# CP_Sapling.net
KiCad netlist of a schematic drawn in EAGLE
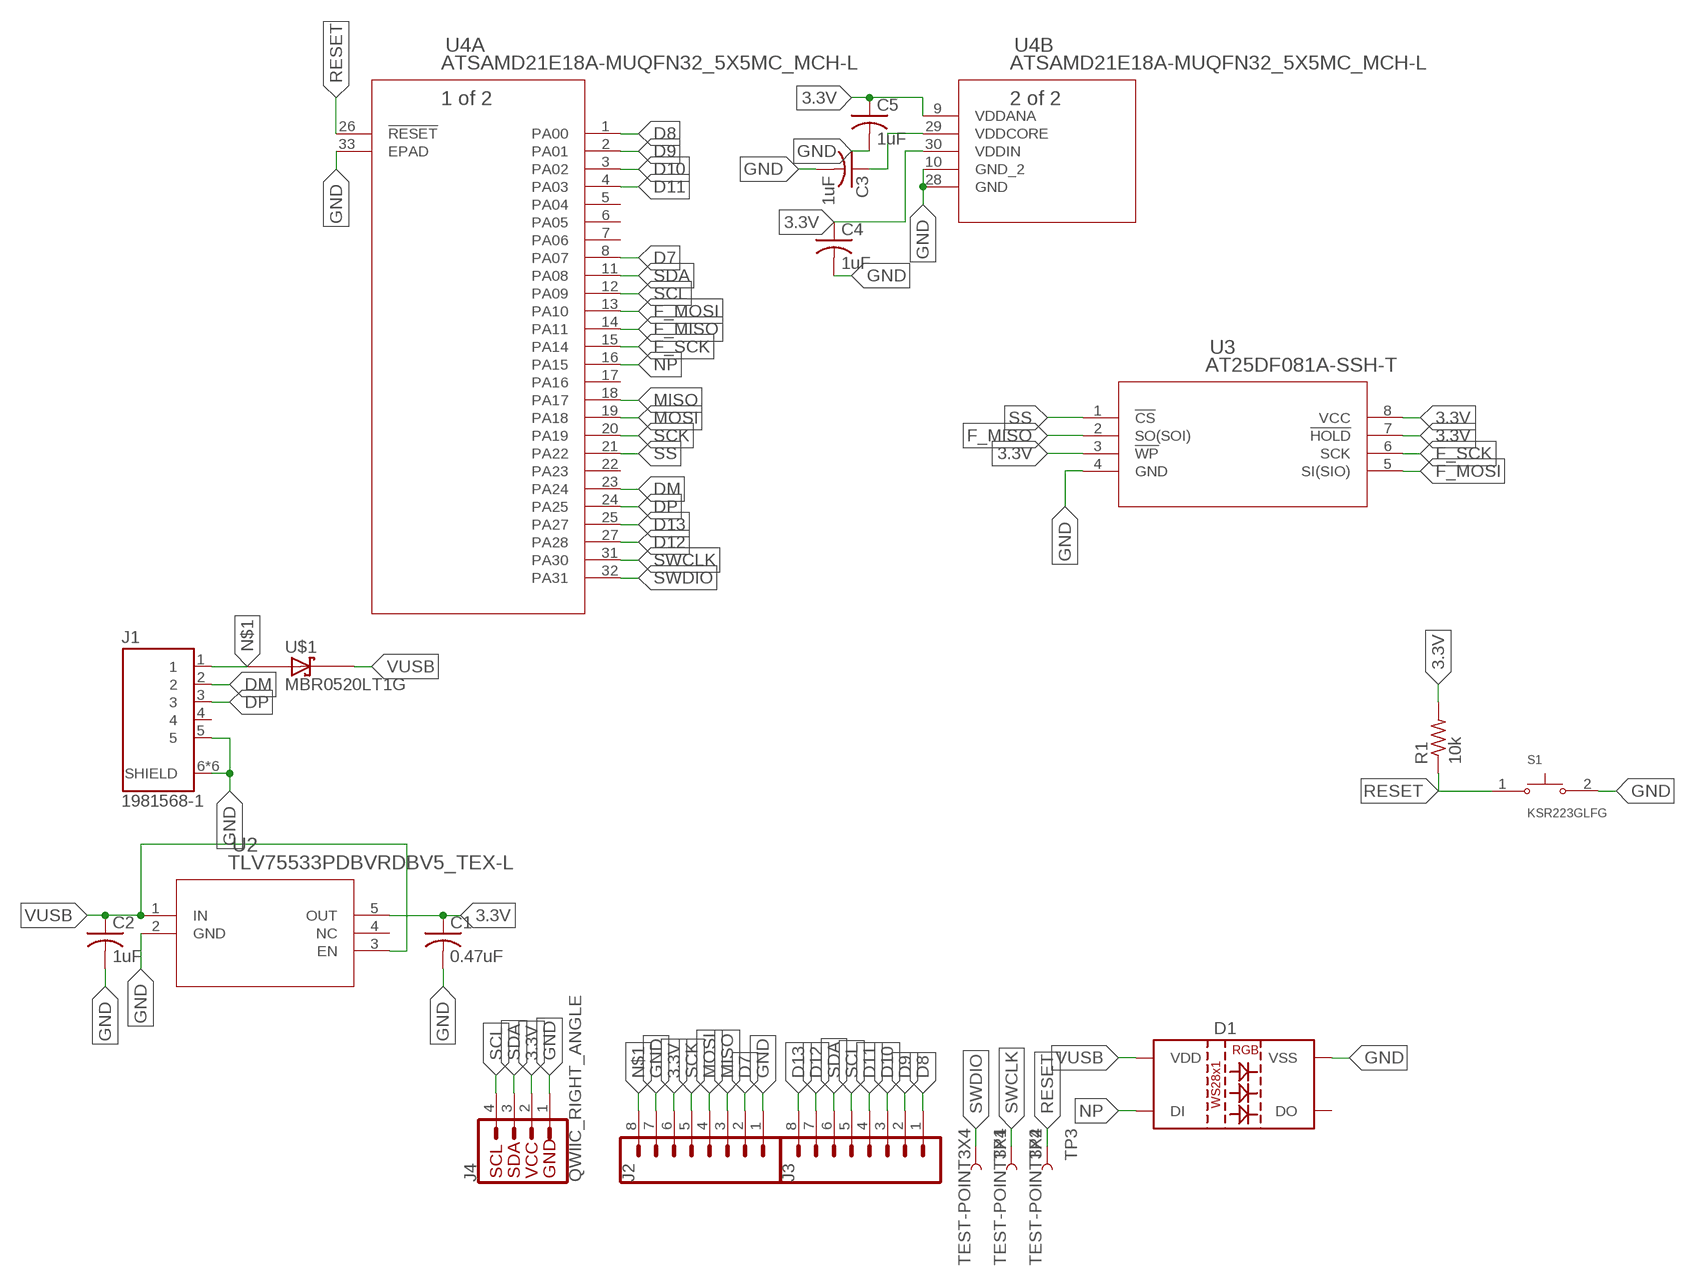
[diagram p0: schematic, sheet 1]

(export (version "E")
  (design (tool "Eeschema 10.0.6"))
  (components
    (comp (ref "C1")
      (value "0.47uF")
      (footprint "eagle-import:C0402")
      (libsource (lib "eagle-import") (part "C-USC0402"))
    )
    (comp (ref "C2")
      (value "1uF")
      (footprint "eagle-import:C0402")
      (libsource (lib "eagle-import") (part "C-USC0402"))
    )
    (comp (ref "C3")
      (value "1uF")
      (footprint "eagle-import:C0402")
      (libsource (lib "eagle-import") (part "C-USC0402"))
    )
    (comp (ref "C4")
      (value "1uF")
      (footprint "eagle-import:C0402")
      (libsource (lib "eagle-import") (part "C-USC0402"))
    )
    (comp (ref "C5")
      (value "1uF")
      (footprint "eagle-import:C0402")
      (libsource (lib "eagle-import") (part "C-USC0402"))
    )
    (comp (ref "D1")
      (value "WS2812B")
      (footprint "eagle-import:WS2812-3535")
      (libsource (lib "eagle-import") (part "WS2812BWS2812B-3535"))
    )
    (comp (ref "J1")
      (value "1981568-1")
      (footprint "eagle-import:TE_1981568-1")
      (fields (field (name "MF") "TE Connectivity") (field (name "MP") "19815681"))
      (libsource (lib "eagle-import") (part "1981568-1"))
    )
    (comp (ref "J2")
      (value "CONN_08NO_SILK_DNP")
      (footprint "eagle-import:1X08_NO_SILK")
      (libsource (lib "eagle-import") (part "CONN_08NO_SILK_DNP"))
    )
    (comp (ref "J3")
      (value "CONN_08NO_SILK_DNP")
      (footprint "eagle-import:1X08_NO_SILK")
      (libsource (lib "eagle-import") (part "CONN_08NO_SILK_DNP"))
    )
    (comp (ref "J4")
      (value "QWIIC_RIGHT_ANGLE")
      (footprint "eagle-import:JST04_1MM_RA")
      (libsource (lib "eagle-import") (part "QWIIC_CONNECTORJS-1MM"))
    )
    (comp (ref "R1")
      (value "10k")
      (footprint "eagle-import:R0402")
      (libsource (lib "eagle-import") (part "R-US_R0402"))
    )
    (comp (ref "S1")
      (value "KSR223GLFG")
      (footprint "eagle-import:SW_KSR223GLFG")
      (fields (field (name "MF") "C&K"))
      (libsource (lib "eagle-import") (part "KSR223GLFG"))
    )
    (comp (ref "TP1")
      (value "TEST-POINT3X4")
      (footprint "eagle-import:PAD.03X.04")
      (libsource (lib "eagle-import") (part "TEST-POINT3X4"))
    )
    (comp (ref "TP2")
      (value "TEST-POINT3X4")
      (footprint "eagle-import:PAD.03X.04")
      (libsource (lib "eagle-import") (part "TEST-POINT3X4"))
    )
    (comp (ref "TP3")
      (value "TEST-POINT3X4")
      (footprint "eagle-import:PAD.03X.04")
      (libsource (lib "eagle-import") (part "TEST-POINT3X4"))
    )
    (comp (ref "U$1")
      (value "MBR0520LT1G")
      (footprint "eagle-import:SOD3716X117(SOD-123)")
      (fields (field (name "MF") "ON Semiconductor"))
      (libsource (lib "eagle-import") (part "MBR0520LT1G"))
    )
    (comp (ref "U2")
      (value "TLV75533PDBVRDBV5_TEX-L")
      (footprint "eagle-import:DBV5_TEX-L")
      (fields
        (field (name "MANUFACTURER_PART_NUMBER") "TLV75533PDBVR")
        (field (name "COPYRIGHT") "Copyright (C) 2018 Accelerated Designs. All rights reserved")
      )
      (libsource (lib "eagle-import") (part "TLV75533PDBVRDBV5_TEX-L"))
    )
    (comp (ref "U3")
      (value "AT25DF081A-SSH-T")
      (footprint "eagle-import:SOIC_AT25DF081_ADO")
      (fields (field (name "COPYRIGHT") "Copyright (C) 2018 Accelerated Designs. All rights reserved"))
      (libsource (lib "eagle-import") (part "AT25DF081A-SSH-T"))
    )
    (comp (ref "U4")
      (value "ATSAMD21E18A-MUQFN32_5X5MC_MCH-L")
      (footprint "eagle-import:QFN32_5X5MC_MCH-L")
      (fields
        (field (name "MANUFACTURER_PART_NUMBER") "ATSAMD21E18A-MU")
        (field (name "COPYRIGHT") "Copyright (C) 2018 Accelerated Designs. All rights reserved")
      )
      (libsource (lib "eagle-import") (part "ATSAMD21E18A-MUQFN32_5X5MC_MCH-L"))
    )
  )
  (nets
    (net (code "1") (name "3.3V") (class "Default")
      (node (ref "C1") (pin "1") (pinfunction "1_1") (pintype "passive"))
      (node (ref "C4") (pin "1") (pinfunction "1_1") (pintype "passive"))
      (node (ref "C5") (pin "1") (pinfunction "1_1") (pintype "passive"))
      (node (ref "J2") (pin "6") (pinfunction "6_6") (pintype "passive"))
      (node (ref "J4") (pin "2") (pinfunction "2_2") (pintype "power_in"))
      (node (ref "R1") (pin "2") (pinfunction "2_2") (pintype "passive"))
      (node (ref "U2") (pin "5") (pinfunction "OUT_5") (pintype "output"))
      (node (ref "U3") (pin "3") (pinfunction "~{WP}_3") (pintype "input"))
      (node (ref "U3") (pin "7") (pinfunction "~{HOLD}_7") (pintype "input"))
      (node (ref "U3") (pin "8") (pinfunction "VCC_8") (pintype "power_in"))
      (node (ref "U4") (pin "30") (pinfunction "VDDIN_30") (pintype "power_in"))
      (node (ref "U4") (pin "9") (pinfunction "VDDANA_9") (pintype "power_in"))
    )
    (net (code "2") (name "D7") (class "Default")
      (node (ref "J2") (pin "2") (pinfunction "2_2") (pintype "passive"))
      (node (ref "U4") (pin "8") (pinfunction "PA07_8") (pintype "bidirectional"))
    )
    (net (code "3") (name "D8") (class "Default")
      (node (ref "J3") (pin "1") (pinfunction "1_1") (pintype "passive"))
      (node (ref "U4") (pin "1") (pinfunction "PA00_1") (pintype "bidirectional"))
    )
    (net (code "4") (name "D9") (class "Default")
      (node (ref "J3") (pin "2") (pinfunction "2_2") (pintype "passive"))
      (node (ref "U4") (pin "2") (pinfunction "PA01_2") (pintype "bidirectional"))
    )
    (net (code "5") (name "D10") (class "Default")
      (node (ref "J3") (pin "3") (pinfunction "3_3") (pintype "passive"))
      (node (ref "U4") (pin "3") (pinfunction "PA02_3") (pintype "bidirectional"))
    )
    (net (code "6") (name "D11") (class "Default")
      (node (ref "J3") (pin "4") (pinfunction "4_4") (pintype "passive"))
      (node (ref "U4") (pin "4") (pinfunction "PA03_4") (pintype "bidirectional"))
    )
    (net (code "7") (name "D12") (class "Default")
      (node (ref "J3") (pin "7") (pinfunction "7_7") (pintype "passive"))
      (node (ref "U4") (pin "27") (pinfunction "PA28_27") (pintype "bidirectional"))
    )
    (net (code "8") (name "D13") (class "Default")
      (node (ref "J3") (pin "8") (pinfunction "8_8") (pintype "passive"))
      (node (ref "U4") (pin "25") (pinfunction "PA27_25") (pintype "bidirectional"))
    )
    (net (code "9") (name "DM") (class "Default")
      (node (ref "J1") (pin "2") (pinfunction "2_2") (pintype "passive"))
      (node (ref "U4") (pin "23") (pinfunction "PA24_23") (pintype "bidirectional"))
    )
    (net (code "10") (name "DP") (class "Default")
      (node (ref "J1") (pin "3") (pinfunction "3_3") (pintype "passive"))
      (node (ref "U4") (pin "24") (pinfunction "PA25_24") (pintype "bidirectional"))
    )
    (net (code "11") (name "F_MISO") (class "Default")
      (node (ref "U3") (pin "2") (pinfunction "SO(SOI)_2") (pintype "bidirectional"))
      (node (ref "U4") (pin "14") (pinfunction "PA11_14") (pintype "bidirectional"))
    )
    (net (code "12") (name "F_MOSI") (class "Default")
      (node (ref "U3") (pin "5") (pinfunction "SI(SIO)_5") (pintype "bidirectional"))
      (node (ref "U4") (pin "13") (pinfunction "PA10_13") (pintype "bidirectional"))
    )
    (net (code "13") (name "F_SCK") (class "Default")
      (node (ref "U3") (pin "6") (pinfunction "SCK_6") (pintype "input"))
      (node (ref "U4") (pin "15") (pinfunction "PA14_15") (pintype "bidirectional"))
    )
    (net (code "14") (name "GND") (class "Default")
      (node (ref "C1") (pin "2") (pinfunction "2_2") (pintype "passive"))
      (node (ref "C2") (pin "2") (pinfunction "2_2") (pintype "passive"))
      (node (ref "C3") (pin "2") (pinfunction "2_2") (pintype "passive"))
      (node (ref "C4") (pin "2") (pinfunction "2_2") (pintype "passive"))
      (node (ref "C5") (pin "2") (pinfunction "2_2") (pintype "passive"))
      (node (ref "D1") (pin "VSS") (pinfunction "VSS_VSS") (pintype "bidirectional"))
      (node (ref "J1") (pin "10") (pinfunction "SHIELD_10") (pintype "passive"))
      (node (ref "J1") (pin "11") (pinfunction "SHIELD_11") (pintype "passive"))
      (node (ref "J1") (pin "5") (pinfunction "5_5") (pintype "passive"))
      (node (ref "J1") (pin "6") (pinfunction "SHIELD_6") (pintype "passive"))
      (node (ref "J1") (pin "7") (pinfunction "SHIELD_7") (pintype "passive"))
      (node (ref "J1") (pin "8") (pinfunction "SHIELD_8") (pintype "passive"))
      (node (ref "J1") (pin "9") (pinfunction "SHIELD_9") (pintype "passive"))
      (node (ref "J2") (pin "1") (pinfunction "1_1") (pintype "passive"))
      (node (ref "J2") (pin "7") (pinfunction "7_7") (pintype "passive"))
      (node (ref "J4") (pin "1") (pinfunction "1_1") (pintype "power_in"))
      (node (ref "S1") (pin "2") (pinfunction "2_2") (pintype "passive"))
      (node (ref "U2") (pin "2") (pinfunction "GND_2") (pintype "power_in"))
      (node (ref "U3") (pin "4") (pinfunction "GND_4") (pintype "power_in"))
      (node (ref "U4") (pin "10") (pinfunction "GND_2_10") (pintype "passive"))
      (node (ref "U4") (pin "28") (pinfunction "GND_28") (pintype "passive"))
      (node (ref "U4") (pin "33") (pinfunction "EPAD_33") (pintype "passive"))
    )
    (net (code "15") (name "MISO") (class "Default")
      (node (ref "J2") (pin "3") (pinfunction "3_3") (pintype "passive"))
      (node (ref "U4") (pin "18") (pinfunction "PA17_18") (pintype "bidirectional"))
    )
    (net (code "16") (name "MOSI") (class "Default")
      (node (ref "J2") (pin "4") (pinfunction "4_4") (pintype "passive"))
      (node (ref "U4") (pin "19") (pinfunction "PA18_19") (pintype "bidirectional"))
    )
    (net (code "17") (name "N$1") (class "Default")
      (node (ref "J1") (pin "1") (pinfunction "1_1") (pintype "passive"))
      (node (ref "J2") (pin "8") (pinfunction "8_8") (pintype "passive"))
      (node (ref "U$1") (pin "2") (pinfunction "A_2") (pintype "passive"))
    )
    (net (code "18") (name "NP") (class "Default")
      (node (ref "D1") (pin "DIN") (pinfunction "DI_DIN") (pintype "bidirectional"))
      (node (ref "U4") (pin "16") (pinfunction "PA15_16") (pintype "bidirectional"))
    )
    (net (code "19") (name "Net-(U4B-VDDCORE)") (class "Default")
      (node (ref "C3") (pin "1") (pinfunction "1_1") (pintype "passive"))
      (node (ref "U4") (pin "29") (pinfunction "VDDCORE_29") (pintype "power_in"))
    )
    (net (code "20") (name "RESET") (class "Default")
      (node (ref "R1") (pin "1") (pinfunction "1_1") (pintype "passive"))
      (node (ref "S1") (pin "1") (pinfunction "1_1") (pintype "passive"))
      (node (ref "TP3") (pin "P$1") (pinfunction "1_P$1") (pintype "bidirectional"))
      (node (ref "U4") (pin "26") (pinfunction "~{RESET}_26") (pintype "passive"))
    )
    (net (code "21") (name "SCK") (class "Default")
      (node (ref "J2") (pin "5") (pinfunction "5_5") (pintype "passive"))
      (node (ref "U4") (pin "20") (pinfunction "PA19_20") (pintype "bidirectional"))
    )
    (net (code "22") (name "SCL") (class "Default")
      (node (ref "J3") (pin "5") (pinfunction "5_5") (pintype "passive"))
      (node (ref "J4") (pin "4") (pinfunction "4_4") (pintype "passive"))
      (node (ref "U4") (pin "12") (pinfunction "PA09_12") (pintype "bidirectional"))
    )
    (net (code "23") (name "SDA") (class "Default")
      (node (ref "J3") (pin "6") (pinfunction "6_6") (pintype "passive"))
      (node (ref "J4") (pin "3") (pinfunction "3_3") (pintype "passive"))
      (node (ref "U4") (pin "11") (pinfunction "PA08_11") (pintype "bidirectional"))
    )
    (net (code "24") (name "SS") (class "Default")
      (node (ref "U3") (pin "1") (pinfunction "~{CS}_1") (pintype "input"))
      (node (ref "U4") (pin "21") (pinfunction "PA22_21") (pintype "bidirectional"))
    )
    (net (code "25") (name "SWCLK") (class "Default")
      (node (ref "TP2") (pin "P$1") (pinfunction "1_P$1") (pintype "bidirectional"))
      (node (ref "U4") (pin "31") (pinfunction "PA30_31") (pintype "bidirectional"))
    )
    (net (code "26") (name "SWDIO") (class "Default")
      (node (ref "TP1") (pin "P$1") (pinfunction "1_P$1") (pintype "bidirectional"))
      (node (ref "U4") (pin "32") (pinfunction "PA31_32") (pintype "bidirectional"))
    )
    (net (code "27") (name "VUSB") (class "Default")
      (node (ref "C2") (pin "1") (pinfunction "1_1") (pintype "passive"))
      (node (ref "D1") (pin "VDD") (pinfunction "VDD_VDD") (pintype "bidirectional"))
      (node (ref "U$1") (pin "1") (pinfunction "C_1") (pintype "passive"))
      (node (ref "U2") (pin "1") (pinfunction "IN_1") (pintype "input"))
      (node (ref "U2") (pin "3") (pinfunction "EN_3") (pintype "input"))
    )
    (net (code "28") (name "unconnected-(D1-DO-PadDOUT)") (class "Default")
      (node (ref "D1") (pin "DOUT") (pinfunction "DO_DOUT") (pintype "bidirectional"))
    )
    (net (code "29") (name "unconnected-(J1-Pad4)") (class "Default")
      (node (ref "J1") (pin "4") (pinfunction "4_4") (pintype "passive"))
    )
    (net (code "30") (name "unconnected-(U2-NC-Pad4)") (class "Default")
      (node (ref "U2") (pin "4") (pinfunction "NC_4") (pintype "no_connect"))
    )
    (net (code "31") (name "unconnected-(U4A-PA04-Pad5)") (class "Default")
      (node (ref "U4") (pin "5") (pinfunction "PA04_5") (pintype "bidirectional"))
    )
    (net (code "32") (name "unconnected-(U4A-PA05-Pad6)") (class "Default")
      (node (ref "U4") (pin "6") (pinfunction "PA05_6") (pintype "bidirectional"))
    )
    (net (code "33") (name "unconnected-(U4A-PA06-Pad7)") (class "Default")
      (node (ref "U4") (pin "7") (pinfunction "PA06_7") (pintype "bidirectional"))
    )
    (net (code "34") (name "unconnected-(U4A-PA16-Pad17)") (class "Default")
      (node (ref "U4") (pin "17") (pinfunction "PA16_17") (pintype "bidirectional"))
    )
    (net (code "35") (name "unconnected-(U4A-PA23-Pad22)") (class "Default")
      (node (ref "U4") (pin "22") (pinfunction "PA23_22") (pintype "bidirectional"))
    )
  )
)
